# 1_P1_schdoc.net
KiCad netlist of a schematic drawn in Altium Designer
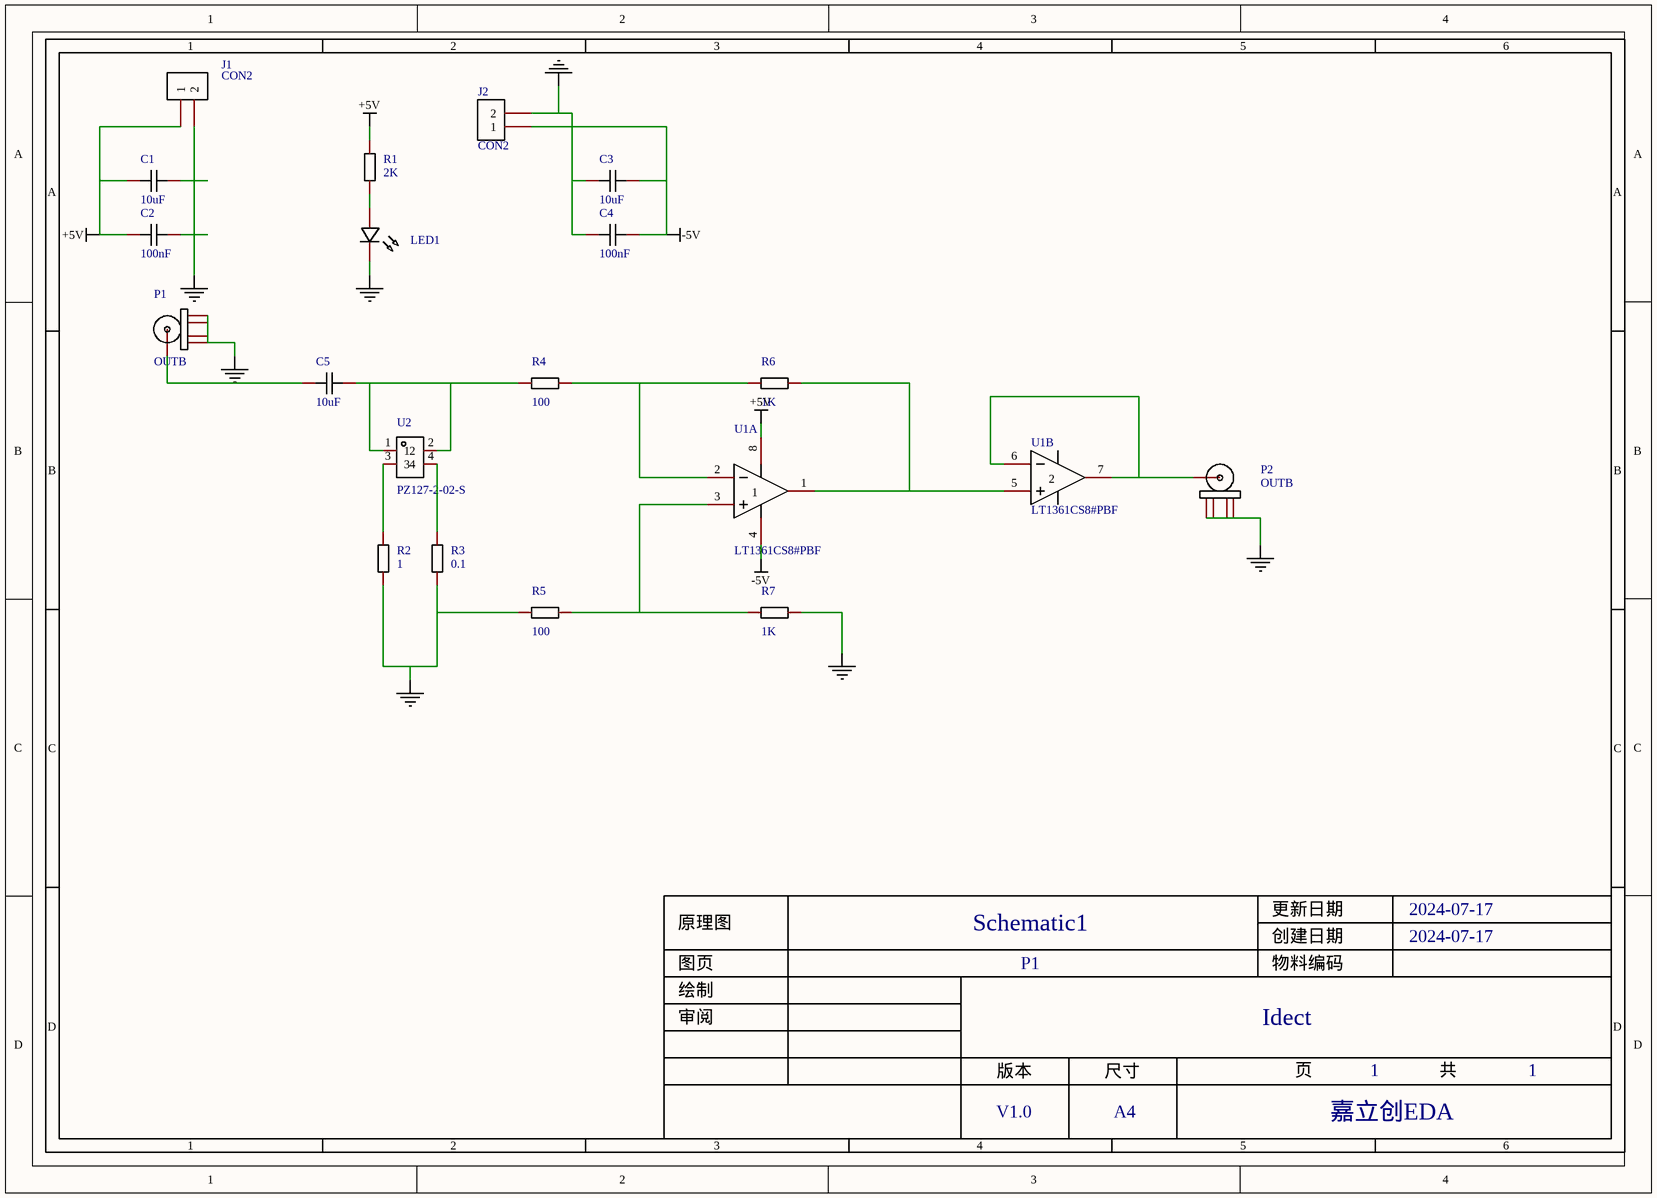
[diagram p0: 1_P1.schdoc.schdoc]

(export (version "E")
  (design (tool "Eeschema 10.0.6"))
  (components
    (comp (ref "C1")
      (value "10uF")
      (fields (field (name "NAME") "10uF"))
      (libsource (lib "altium-import") (part "root_0_CAP_0805_"))
    )
    (comp (ref "C2")
      (value "100nF")
      (fields (field (name "NAME") "100nF"))
      (libsource (lib "altium-import") (part "root_0_CAP_0805_"))
    )
    (comp (ref "C3")
      (value "10uF")
      (fields (field (name "NAME") "10uF"))
      (libsource (lib "altium-import") (part "root_0_CAP_0805_"))
    )
    (comp (ref "C4")
      (value "100nF")
      (fields (field (name "NAME") "100nF"))
      (libsource (lib "altium-import") (part "root_0_CAP_0805_"))
    )
    (comp (ref "C5")
      (value "10uF")
      (fields (field (name "NAME") "10uF"))
      (libsource (lib "altium-import") (part "root_0_CAP_0805_"))
    )
    (comp (ref "J1")
      (value "CON2")
      (fields (field (name "NAME") "CON2"))
      (libsource (lib "altium-import") (part "root_0_CON2_"))
    )
    (comp (ref "J2")
      (value "CON2")
      (fields (field (name "NAME") "CON2"))
      (libsource (lib "altium-import") (part "root_1_CON2_"))
    )
    (comp (ref "LED1") (value "LED_0805-R") (libsource (lib "altium-import") (part "root_3_LED_0805-R_")))
    (comp (ref "P1")
      (value "OUTB")
      (fields (field (name "NAME") "OUTB"))
      (libsource (lib "altium-import") (part "root_1_BNC_"))
    )
    (comp (ref "P2")
      (value "OUTB")
      (fields (field (name "NAME") "OUTB"))
      (libsource (lib "altium-import") (part "root_0_BNC_"))
    )
    (comp (ref "R1")
      (value "2K")
      (fields (field (name "NAME") "2K"))
      (libsource (lib "altium-import") (part "root_3_Res_0805_"))
    )
    (comp (ref "R2")
      (value "1")
      (fields (field (name "NAME") "1"))
      (libsource (lib "altium-import") (part "root_1_Res_0805_"))
    )
    (comp (ref "R3")
      (value "0.1")
      (fields (field (name "NAME") "0.1"))
      (libsource (lib "altium-import") (part "root_1_Res_0805_"))
    )
    (comp (ref "R4")
      (value "100")
      (fields (field (name "NAME") "100"))
      (libsource (lib "altium-import") (part "root_0_Res_0805_"))
    )
    (comp (ref "R5")
      (value "100")
      (fields (field (name "NAME") "100"))
      (libsource (lib "altium-import") (part "root_0_Res_0805_"))
    )
    (comp (ref "R6")
      (value "1K")
      (fields (field (name "NAME") "1K"))
      (libsource (lib "altium-import") (part "root_0_Res_0805_"))
    )
    (comp (ref "R7")
      (value "1K")
      (fields (field (name "NAME") "1K"))
      (libsource (lib "altium-import") (part "root_0_Res_0805_"))
    )
    (comp (ref "U1")
      (value "LT1361CS8#PBF")
      (description "放大器数:双路;增益带宽积(GBP):50MHz;输入偏置电流(Ib):300nA;压摆率(SR):800V/us;带宽(-3db):-;")
      (fields (field (name "NAME") "LT1361CS8#PBF") (field (name "MANUFACTURER") "ADI(亚德诺)"))
      (libsource (lib "altium-import") (part "root_0_LT1361CS8#PBF_"))
    )
    (comp (ref "U2")
      (value "PZ127-2-02-S")
      (fields (field (name "NAME") "PZ127-2-02-S") (field (name "MANUFACTURER") "HCTL(华灿天禄)"))
      (libsource (lib "altium-import") (part "root_0_PZ127-2-02-S_"))
    )
  )
  (nets
    (net (code "1") (name "+5V") (class "Default")
      (node (ref "C1") (pin "1") (pinfunction "1_1") (pintype "passive"))
      (node (ref "C2") (pin "1") (pinfunction "1_1") (pintype "passive"))
      (node (ref "J1") (pin "1") (pinfunction "1_1") (pintype "passive"))
      (node (ref "R1") (pin "1") (pinfunction "1_1") (pintype "passive"))
      (node (ref "U1") (pin "8") (pinfunction "V+_8") (pintype "passive"))
    )
    (net (code "2") (name "-5V") (class "Default")
      (node (ref "C3") (pin "2") (pinfunction "2_2") (pintype "passive"))
      (node (ref "C4") (pin "2") (pinfunction "2_2") (pintype "passive"))
      (node (ref "J2") (pin "1") (pinfunction "1_1") (pintype "passive"))
      (node (ref "U1") (pin "4") (pinfunction "V-_4") (pintype "passive"))
    )
    (net (code "3") (name "GND") (class "Default")
      (node (ref "C1") (pin "2") (pinfunction "2_2") (pintype "passive"))
      (node (ref "C2") (pin "2") (pinfunction "2_2") (pintype "passive"))
      (node (ref "C3") (pin "1") (pinfunction "1_1") (pintype "passive"))
      (node (ref "C4") (pin "1") (pinfunction "1_1") (pintype "passive"))
      (node (ref "J1") (pin "2") (pinfunction "2_2") (pintype "passive"))
      (node (ref "J2") (pin "2") (pinfunction "2_2") (pintype "passive"))
      (node (ref "LED1") (pin "1") (pinfunction "C_1") (pintype "passive"))
      (node (ref "P1") (pin "2") (pinfunction "GND_2") (pintype "passive"))
      (node (ref "P1") (pin "3") (pinfunction "GND_3") (pintype "passive"))
      (node (ref "P1") (pin "4") (pinfunction "GND_4") (pintype "passive"))
      (node (ref "P1") (pin "5") (pinfunction "GND_5") (pintype "passive"))
      (node (ref "P2") (pin "2") (pinfunction "GND_2") (pintype "passive"))
      (node (ref "P2") (pin "3") (pinfunction "GND_3") (pintype "passive"))
      (node (ref "P2") (pin "4") (pinfunction "GND_4") (pintype "passive"))
      (node (ref "P2") (pin "5") (pinfunction "GND_5") (pintype "passive"))
      (node (ref "R2") (pin "1") (pinfunction "1_1") (pintype "passive"))
      (node (ref "R3") (pin "1") (pinfunction "1_1") (pintype "passive"))
      (node (ref "R5") (pin "1") (pinfunction "1_1") (pintype "passive"))
      (node (ref "R7") (pin "2") (pinfunction "2_2") (pintype "passive"))
    )
    (net (code "4") (name "Net-(C5-Pad2)") (class "Default")
      (node (ref "C5") (pin "2") (pinfunction "2_2") (pintype "passive"))
      (node (ref "R4") (pin "1") (pinfunction "1_1") (pintype "passive"))
      (node (ref "U2") (pin "1") (pinfunction "1_1") (pintype "passive"))
      (node (ref "U2") (pin "2") (pinfunction "2_2") (pintype "passive"))
    )
    (net (code "5") (name "Net-(LED1-A)") (class "Default")
      (node (ref "LED1") (pin "2") (pinfunction "A_2") (pintype "passive"))
      (node (ref "R1") (pin "2") (pinfunction "2_2") (pintype "passive"))
    )
    (net (code "6") (name "Net-(P1-X)") (class "Default")
      (node (ref "C5") (pin "1") (pinfunction "1_1") (pintype "passive"))
      (node (ref "P1") (pin "1") (pinfunction "X_1") (pintype "passive"))
    )
    (net (code "7") (name "Net-(P2-X)") (class "Default")
      (node (ref "P2") (pin "1") (pinfunction "X_1") (pintype "passive"))
      (node (ref "U1") (pin "6") (pinfunction "INB-_6") (pintype "passive"))
      (node (ref "U1") (pin "7") (pinfunction "OUTB_7") (pintype "passive"))
    )
    (net (code "8") (name "Net-(R2-Pad2)") (class "Default")
      (node (ref "R2") (pin "2") (pinfunction "2_2") (pintype "passive"))
      (node (ref "U2") (pin "3") (pinfunction "3_3") (pintype "passive"))
    )
    (net (code "9") (name "Net-(R3-Pad2)") (class "Default")
      (node (ref "R3") (pin "2") (pinfunction "2_2") (pintype "passive"))
      (node (ref "U2") (pin "4") (pinfunction "4_4") (pintype "passive"))
    )
    (net (code "10") (name "Net-(U1A-INA+)") (class "Default")
      (node (ref "R5") (pin "2") (pinfunction "2_2") (pintype "passive"))
      (node (ref "R7") (pin "1") (pinfunction "1_1") (pintype "passive"))
      (node (ref "U1") (pin "3") (pinfunction "INA+_3") (pintype "passive"))
    )
    (net (code "11") (name "Net-(U1A-INA-)") (class "Default")
      (node (ref "R4") (pin "2") (pinfunction "2_2") (pintype "passive"))
      (node (ref "R6") (pin "1") (pinfunction "1_1") (pintype "passive"))
      (node (ref "U1") (pin "2") (pinfunction "INA-_2") (pintype "passive"))
    )
    (net (code "12") (name "Net-(U1A-OUTA)") (class "Default")
      (node (ref "R6") (pin "2") (pinfunction "2_2") (pintype "passive"))
      (node (ref "U1") (pin "1") (pinfunction "OUTA_1") (pintype "passive"))
      (node (ref "U1") (pin "5") (pinfunction "INB+_5") (pintype "passive"))
    )
  )
)
